# Sheet1.net
KiCad netlist of a schematic drawn in Altium Designer
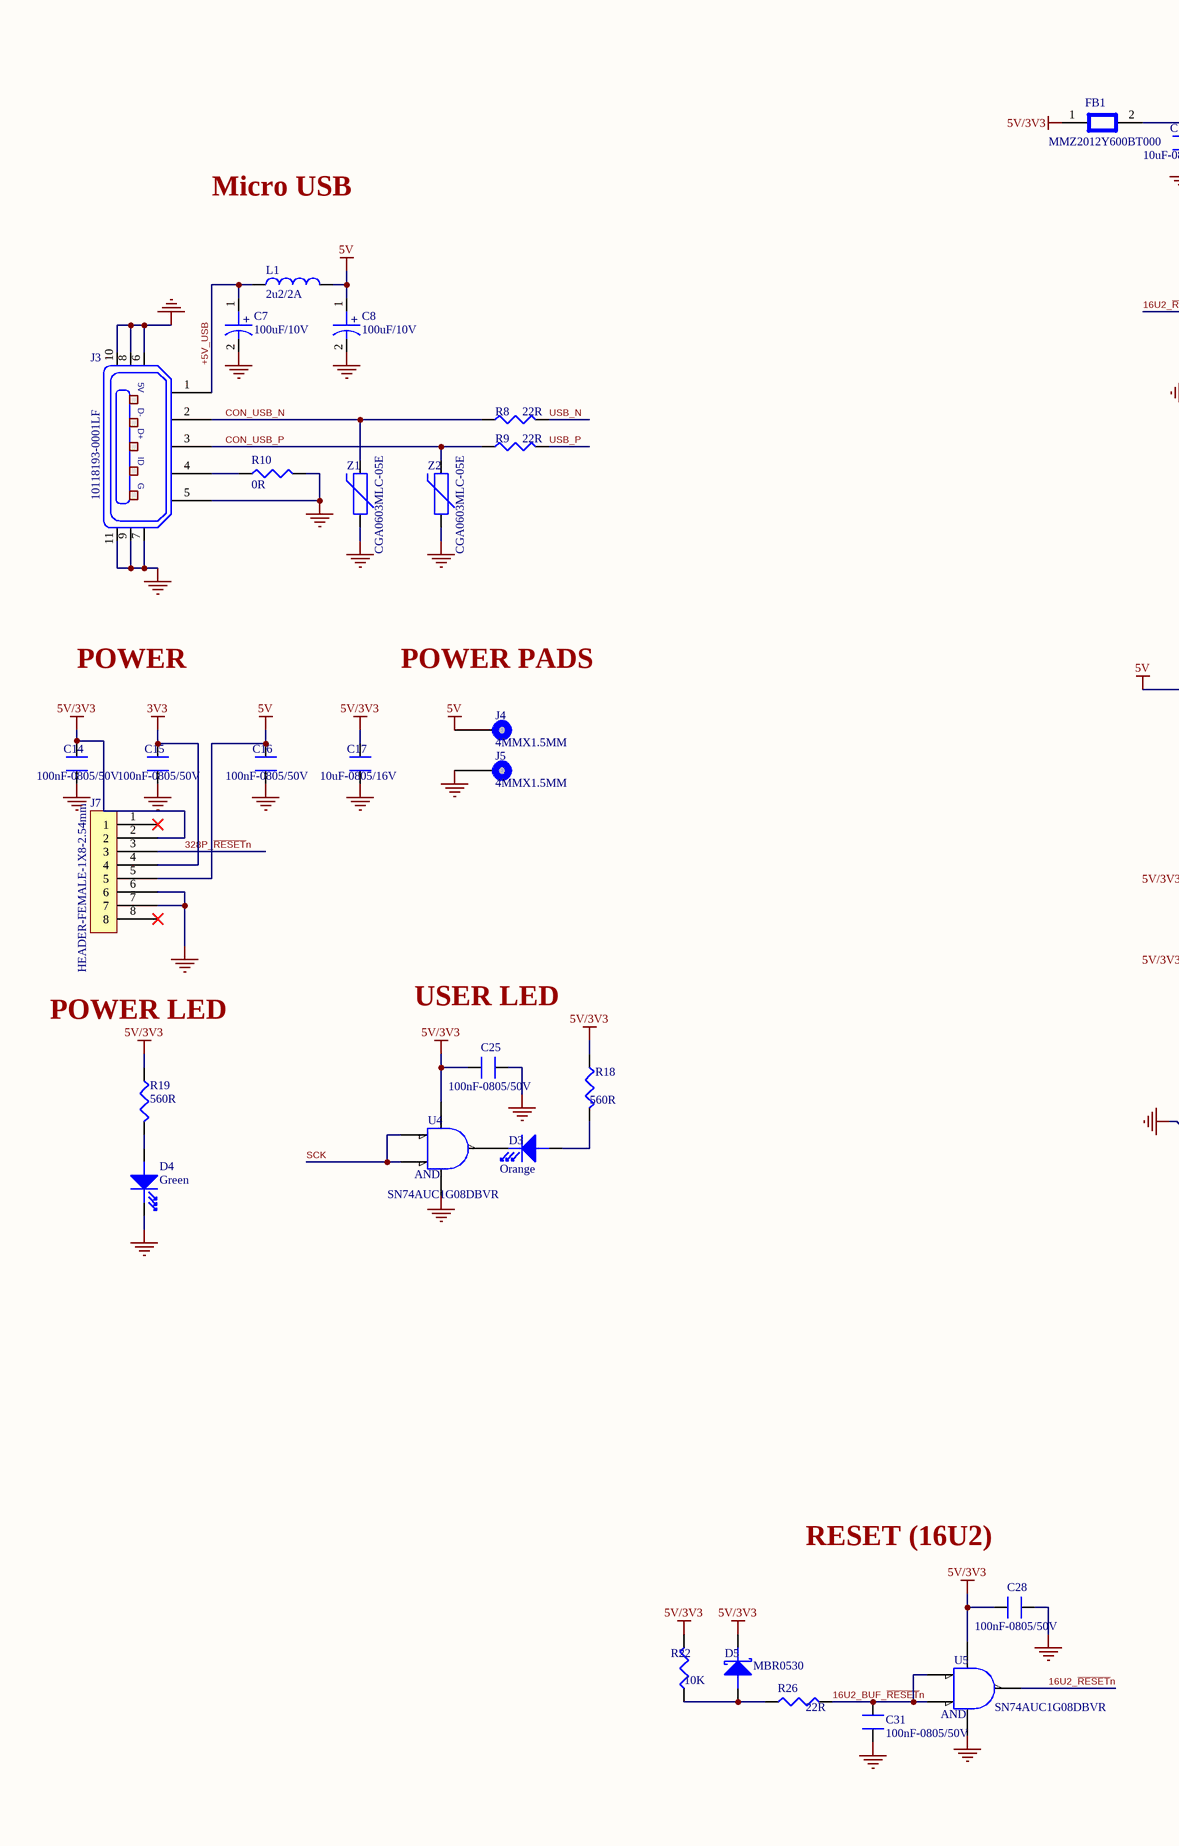
[diagram p0: Sheet1.SchDoc, left]
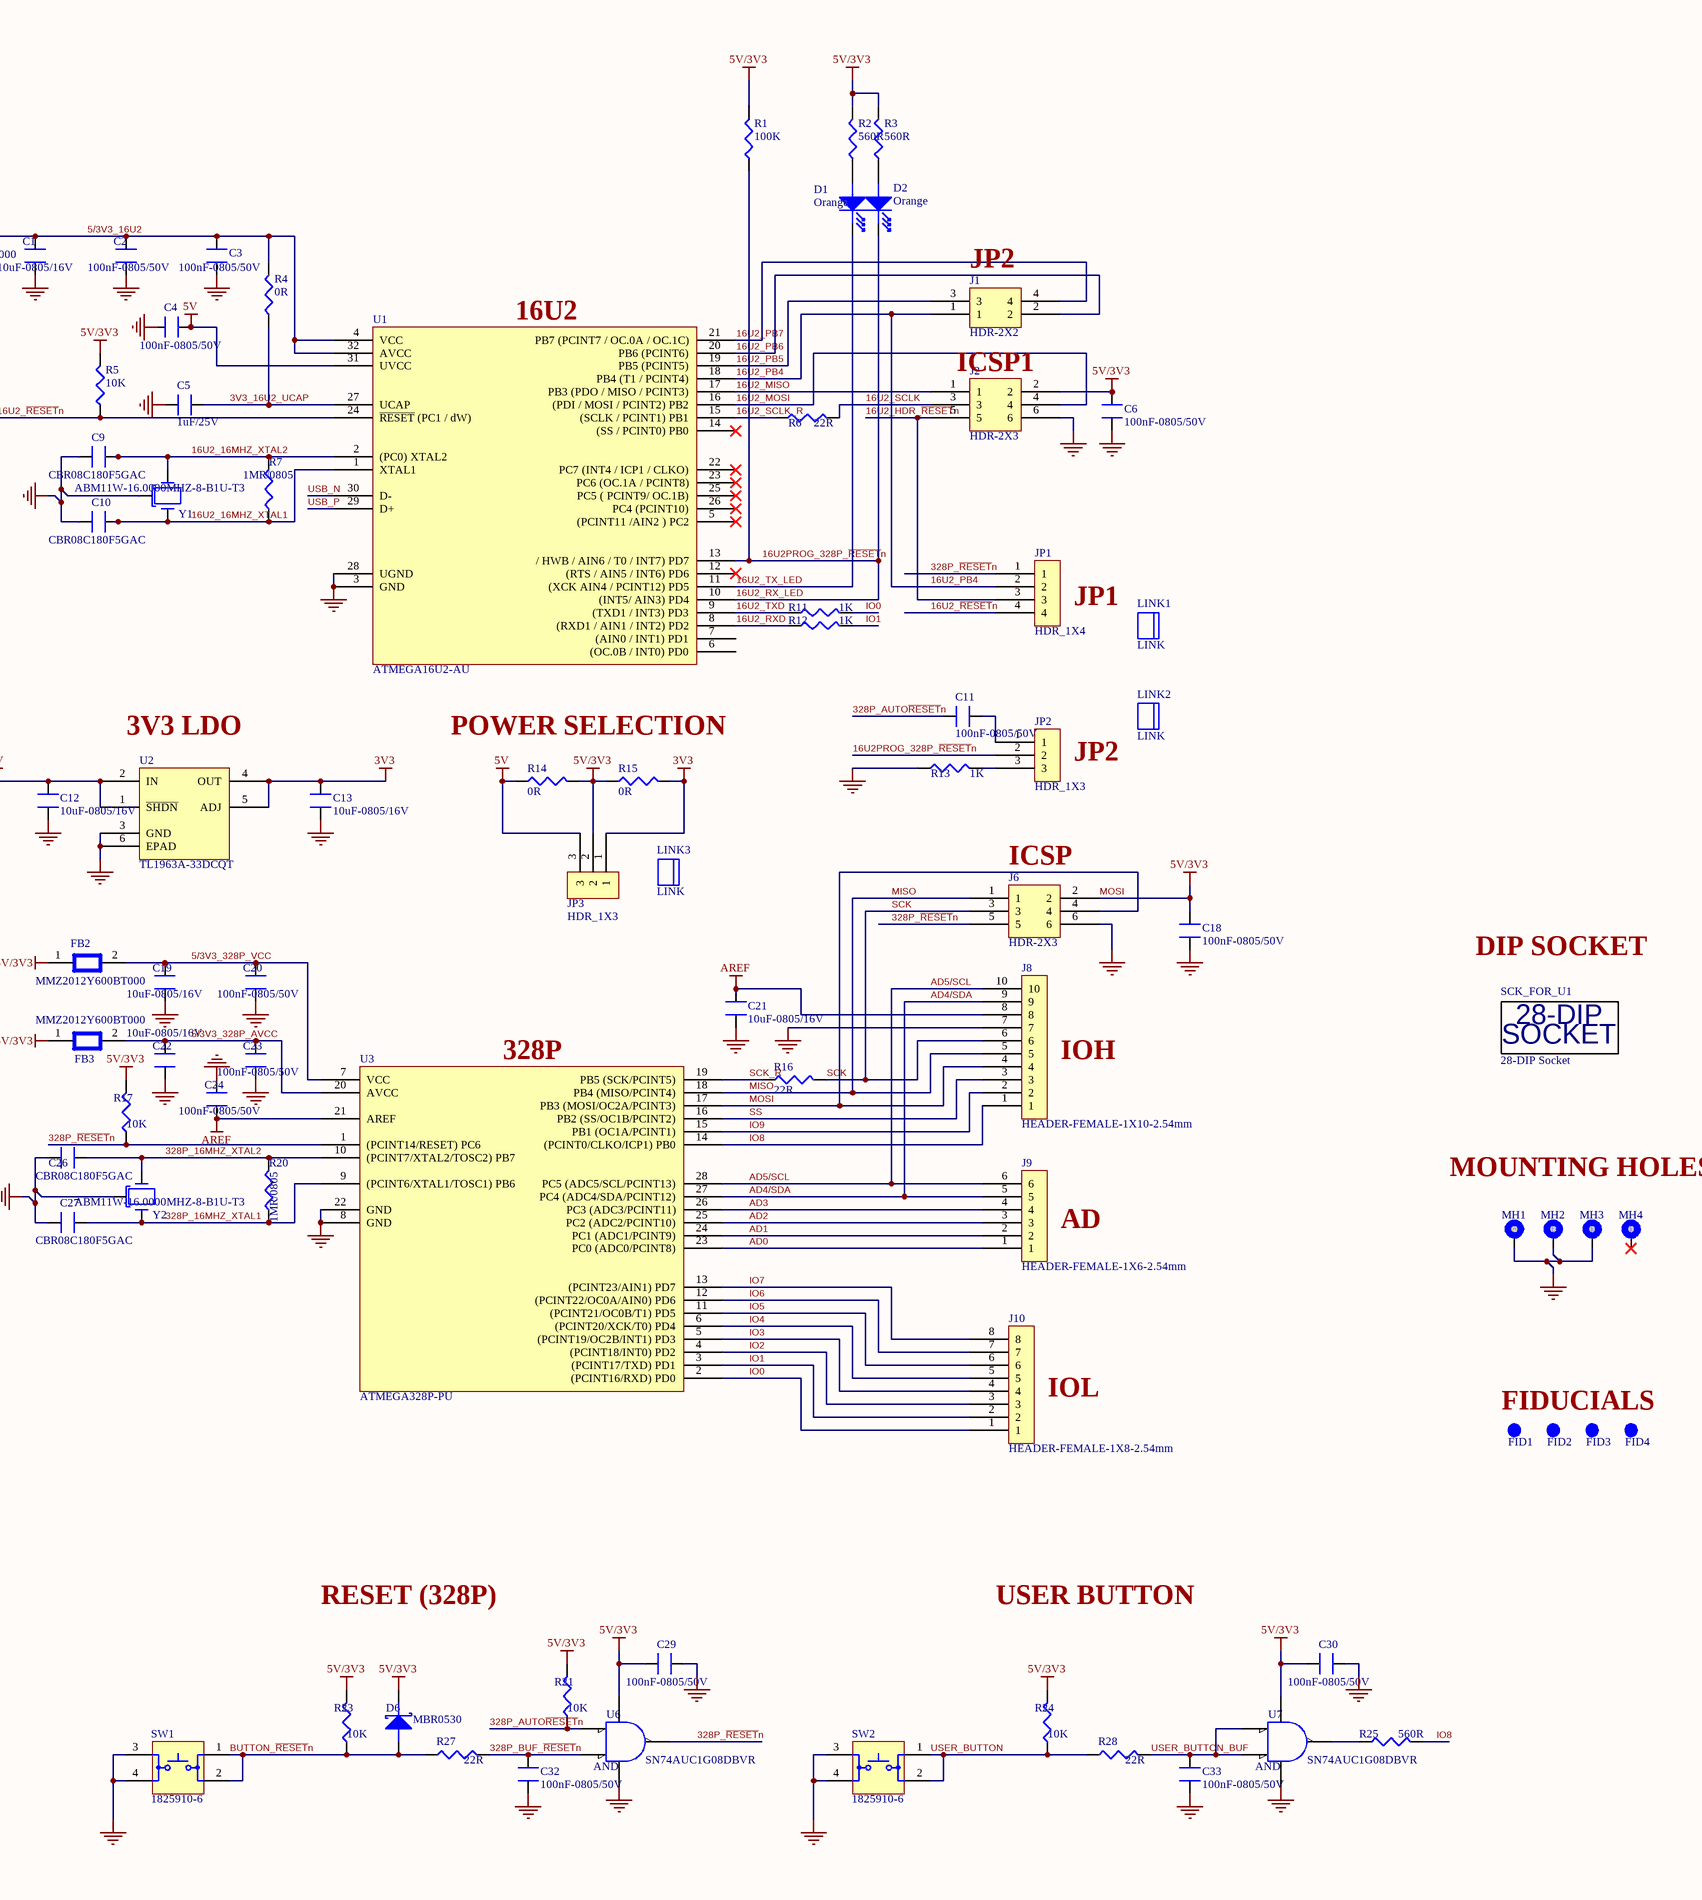
[diagram p1: Sheet1.SchDoc, right]

(export (version "E")
  (design (tool "Eeschema 10.0.6"))
  (components
    (comp (ref "C1")
      (value "10uF-0805/16V")
      (footprint "C0805")
      (fields
        (field (name "MANUFACTURER") "TDK")
        (field (name "MANUFACTURER PART NUMBER") "C2012X5R1C106M085AC")
        (field (name "TOLERANCE") "20%")
      )
      (libsource (lib "Schlib1") (part "C2012X5R1C106M085AC"))
    )
    (comp (ref "C2")
      (value "100nF-0805/50V")
      (footprint "C0805")
      (fields
        (field (name "MANUFACTURER") "TDK")
        (field (name "MANUFACTURER PART NUMBER") "C2012X7R1H104K125AE")
        (field (name "TOLERANCE") "10%")
      )
      (libsource (lib "Schlib1") (part "C2012X7R1H104K125AE"))
    )
    (comp (ref "C3")
      (value "100nF-0805/50V")
      (footprint "C0805")
      (fields
        (field (name "MANUFACTURER") "TDK")
        (field (name "MANUFACTURER PART NUMBER") "C2012X7R1H104K125AE")
        (field (name "TOLERANCE") "10%")
      )
      (libsource (lib "Schlib1") (part "C2012X7R1H104K125AE"))
    )
    (comp (ref "C4")
      (value "100nF-0805/50V")
      (footprint "C0805")
      (fields
        (field (name "MANUFACTURER") "TDK")
        (field (name "MANUFACTURER PART NUMBER") "C2012X7R1H104K125AE")
        (field (name "TOLERANCE") "10%")
      )
      (libsource (lib "Schlib1") (part "C2012X7R1H104K125AE"))
    )
    (comp (ref "C5")
      (value "1uF/25V")
      (footprint "C0805")
      (description "CAP CER 1UF 25V JB 0805")
      (fields
        (field (name "MANUFACTURER") "TDK")
        (field (name "MANUFACTURER PART NUMBER") "CGB4B3JB1E105K055AB")
      )
      (libsource (lib "Schlib1") (part "CGB4B3JB1E105K055AB"))
    )
    (comp (ref "C6")
      (value "100nF-0805/50V")
      (footprint "C0805")
      (fields
        (field (name "MANUFACTURER") "TDK")
        (field (name "MANUFACTURER PART NUMBER") "C2012X7R1H104K125AE")
        (field (name "TOLERANCE") "10%")
      )
      (libsource (lib "Schlib1") (part "C2012X7R1H104K125AE"))
    )
    (comp (ref "C7")
      (value "100uF/10V")
      (footprint "C_ALU_E_SIZE")
      (description "Cap Aluminum Lytic 100uF 10V 20% (8 X 6.2mm) SMD 110mA 1000h 105C T/R")
      (fields
        (field (name "MANUFACTURER") "Panasonic")
        (field (name "MANUFACTURER PART NUMBER") "EEE-HA1A101AP")
      )
      (libsource (lib "Schlib1") (part "EEE-HA1A101AP"))
    )
    (comp (ref "C8")
      (value "100uF/10V")
      (footprint "C_ALU_E_SIZE")
      (description "Cap Aluminum Lytic 100uF 10V 20% (8 X 6.2mm) SMD 110mA 1000h 105C T/R")
      (fields
        (field (name "MANUFACTURER") "Panasonic")
        (field (name "MANUFACTURER PART NUMBER") "EEE-HA1A101AP")
      )
      (libsource (lib "Schlib1") (part "EEE-HA1A101AP"))
    )
    (comp (ref "C9")
      (value "CBR08C180F5GAC")
      (footprint "C0805")
      (description "CAP CER 18PF 50V NP0 0805")
      (fields (field (name "MANUFACTURER") "KEMET") (field (name "TOLERANCE") "1%"))
      (libsource (lib "Schlib1") (part "CBR08C180F5GAC"))
    )
    (comp (ref "C10")
      (value "CBR08C180F5GAC")
      (footprint "C0805")
      (description "CAP CER 18PF 50V NP0 0805")
      (fields (field (name "MANUFACTURER") "KEMET") (field (name "TOLERANCE") "1%"))
      (libsource (lib "Schlib1") (part "CBR08C180F5GAC"))
    )
    (comp (ref "C11")
      (value "100nF-0805/50V")
      (footprint "C0805")
      (fields
        (field (name "MANUFACTURER") "TDK")
        (field (name "MANUFACTURER PART NUMBER") "C2012X7R1H104K125AE")
        (field (name "TOLERANCE") "10%")
      )
      (libsource (lib "Schlib1") (part "C2012X7R1H104K125AE"))
    )
    (comp (ref "C12")
      (value "10uF-0805/16V")
      (footprint "C0805")
      (fields
        (field (name "MANUFACTURER") "TDK")
        (field (name "MANUFACTURER PART NUMBER") "C2012X5R1C106M085AC")
        (field (name "TOLERANCE") "20%")
      )
      (libsource (lib "Schlib1") (part "C2012X5R1C106M085AC"))
    )
    (comp (ref "C13")
      (value "10uF-0805/16V")
      (footprint "C0805")
      (fields
        (field (name "MANUFACTURER") "TDK")
        (field (name "MANUFACTURER PART NUMBER") "C2012X5R1C106M085AC")
        (field (name "TOLERANCE") "20%")
      )
      (libsource (lib "Schlib1") (part "C2012X5R1C106M085AC"))
    )
    (comp (ref "C14")
      (value "100nF-0805/50V")
      (footprint "C0805")
      (fields
        (field (name "MANUFACTURER") "TDK")
        (field (name "MANUFACTURER PART NUMBER") "C2012X7R1H104K125AE")
        (field (name "TOLERANCE") "10%")
      )
      (libsource (lib "Schlib1") (part "C2012X7R1H104K125AE"))
    )
    (comp (ref "C15")
      (value "100nF-0805/50V")
      (footprint "C0805")
      (fields
        (field (name "MANUFACTURER") "TDK")
        (field (name "MANUFACTURER PART NUMBER") "C2012X7R1H104K125AE")
        (field (name "TOLERANCE") "10%")
      )
      (libsource (lib "Schlib1") (part "C2012X7R1H104K125AE"))
    )
    (comp (ref "C16")
      (value "100nF-0805/50V")
      (footprint "C0805")
      (fields
        (field (name "MANUFACTURER") "TDK")
        (field (name "MANUFACTURER PART NUMBER") "C2012X7R1H104K125AE")
        (field (name "TOLERANCE") "10%")
      )
      (libsource (lib "Schlib1") (part "C2012X7R1H104K125AE"))
    )
    (comp (ref "C17")
      (value "10uF-0805/16V")
      (footprint "C0805")
      (fields
        (field (name "MANUFACTURER") "TDK")
        (field (name "MANUFACTURER PART NUMBER") "C2012X5R1C106M085AC")
        (field (name "TOLERANCE") "20%")
      )
      (libsource (lib "Schlib1") (part "C2012X5R1C106M085AC"))
    )
    (comp (ref "C18")
      (value "100nF-0805/50V")
      (footprint "C0805")
      (fields
        (field (name "MANUFACTURER") "TDK")
        (field (name "MANUFACTURER PART NUMBER") "C2012X7R1H104K125AE")
        (field (name "TOLERANCE") "10%")
      )
      (libsource (lib "Schlib1") (part "C2012X7R1H104K125AE"))
    )
    (comp (ref "C19")
      (value "10uF-0805/16V")
      (footprint "C0805")
      (fields
        (field (name "MANUFACTURER") "TDK")
        (field (name "MANUFACTURER PART NUMBER") "C2012X5R1C106M085AC")
        (field (name "TOLERANCE") "20%")
      )
      (libsource (lib "Schlib1") (part "C2012X5R1C106M085AC"))
    )
    (comp (ref "C20")
      (value "100nF-0805/50V")
      (footprint "C0805")
      (fields
        (field (name "MANUFACTURER") "TDK")
        (field (name "MANUFACTURER PART NUMBER") "C2012X7R1H104K125AE")
        (field (name "TOLERANCE") "10%")
      )
      (libsource (lib "Schlib1") (part "C2012X7R1H104K125AE"))
    )
    (comp (ref "C21")
      (value "10uF-0805/16V")
      (footprint "C0805")
      (fields
        (field (name "MANUFACTURER") "TDK")
        (field (name "MANUFACTURER PART NUMBER") "C2012X5R1C106M085AC")
        (field (name "TOLERANCE") "20%")
      )
      (libsource (lib "Schlib1") (part "C2012X5R1C106M085AC"))
    )
    (comp (ref "C22")
      (value "10uF-0805/16V")
      (footprint "C0805")
      (fields
        (field (name "MANUFACTURER") "TDK")
        (field (name "MANUFACTURER PART NUMBER") "C2012X5R1C106M085AC")
        (field (name "TOLERANCE") "20%")
      )
      (libsource (lib "Schlib1") (part "C2012X5R1C106M085AC"))
    )
    (comp (ref "C23")
      (value "100nF-0805/50V")
      (footprint "C0805")
      (fields
        (field (name "MANUFACTURER") "TDK")
        (field (name "MANUFACTURER PART NUMBER") "C2012X7R1H104K125AE")
        (field (name "TOLERANCE") "10%")
      )
      (libsource (lib "Schlib1") (part "C2012X7R1H104K125AE"))
    )
    (comp (ref "C24")
      (value "100nF-0805/50V")
      (footprint "C0805")
      (fields
        (field (name "MANUFACTURER") "TDK")
        (field (name "MANUFACTURER PART NUMBER") "C2012X7R1H104K125AE")
        (field (name "TOLERANCE") "10%")
      )
      (libsource (lib "Schlib1") (part "C2012X7R1H104K125AE"))
    )
    (comp (ref "C25")
      (value "100nF-0805/50V")
      (footprint "C0805")
      (fields
        (field (name "MANUFACTURER") "TDK")
        (field (name "MANUFACTURER PART NUMBER") "C2012X7R1H104K125AE")
        (field (name "TOLERANCE") "10%")
      )
      (libsource (lib "Schlib1") (part "C2012X7R1H104K125AE"))
    )
    (comp (ref "C26")
      (value "CBR08C180F5GAC")
      (footprint "C0805")
      (description "CAP CER 18PF 50V NP0 0805")
      (fields (field (name "MANUFACTURER") "KEMET") (field (name "TOLERANCE") "1%"))
      (libsource (lib "Schlib1") (part "CBR08C180F5GAC"))
    )
    (comp (ref "C27")
      (value "CBR08C180F5GAC")
      (footprint "C0805")
      (description "CAP CER 18PF 50V NP0 0805")
      (fields (field (name "MANUFACTURER") "KEMET") (field (name "TOLERANCE") "1%"))
      (libsource (lib "Schlib1") (part "CBR08C180F5GAC"))
    )
    (comp (ref "C28")
      (value "100nF-0805/50V")
      (footprint "C0805")
      (fields
        (field (name "MANUFACTURER") "TDK")
        (field (name "MANUFACTURER PART NUMBER") "C2012X7R1H104K125AE")
        (field (name "TOLERANCE") "10%")
      )
      (libsource (lib "Schlib1") (part "C2012X7R1H104K125AE"))
    )
    (comp (ref "C29")
      (value "100nF-0805/50V")
      (footprint "C0805")
      (fields
        (field (name "MANUFACTURER") "TDK")
        (field (name "MANUFACTURER PART NUMBER") "C2012X7R1H104K125AE")
        (field (name "TOLERANCE") "10%")
      )
      (libsource (lib "Schlib1") (part "C2012X7R1H104K125AE"))
    )
    (comp (ref "C30")
      (value "100nF-0805/50V")
      (footprint "C0805")
      (fields
        (field (name "MANUFACTURER") "TDK")
        (field (name "MANUFACTURER PART NUMBER") "C2012X7R1H104K125AE")
        (field (name "TOLERANCE") "10%")
      )
      (libsource (lib "Schlib1") (part "C2012X7R1H104K125AE"))
    )
    (comp (ref "C31")
      (value "100nF-0805/50V")
      (footprint "C0805")
      (fields
        (field (name "MANUFACTURER") "TDK")
        (field (name "MANUFACTURER PART NUMBER") "C2012X7R1H104K125AE")
        (field (name "TOLERANCE") "10%")
      )
      (libsource (lib "Schlib1") (part "C2012X7R1H104K125AE"))
    )
    (comp (ref "C32")
      (value "100nF-0805/50V")
      (footprint "C0805")
      (fields
        (field (name "MANUFACTURER") "TDK")
        (field (name "MANUFACTURER PART NUMBER") "C2012X7R1H104K125AE")
        (field (name "TOLERANCE") "10%")
      )
      (libsource (lib "Schlib1") (part "C2012X7R1H104K125AE"))
    )
    (comp (ref "C33")
      (value "100nF-0805/50V")
      (footprint "C0805")
      (fields
        (field (name "MANUFACTURER") "TDK")
        (field (name "MANUFACTURER PART NUMBER") "C2012X7R1H104K125AE")
        (field (name "TOLERANCE") "10%")
      )
      (libsource (lib "Schlib1") (part "C2012X7R1H104K125AE"))
    )
    (comp (ref "D1")
      (value "Orange")
      (footprint "LED-0603")
      (description "OSRAM - LO L29K-H2K1-24-Z - SMARTLED 0603 ORANGE 55AC2374")
      (fields
        (field (name "MANUFACTURER") "Osram Opto")
        (field (name "MANUFACTURER PART NUMBER") "LOL29K-H2K1-24-Z")
      )
      (libsource (lib "Schlib1") (part "LOL29K-H2K1-24-Z"))
    )
    (comp (ref "D2")
      (value "Orange")
      (footprint "LED-0603")
      (description "OSRAM - LO L29K-H2K1-24-Z - SMARTLED 0603 ORANGE 55AC2374")
      (fields
        (field (name "MANUFACTURER") "Osram Opto")
        (field (name "MANUFACTURER PART NUMBER") "LOL29K-H2K1-24-Z")
      )
      (libsource (lib "Schlib1") (part "LOL29K-H2K1-24-Z"))
    )
    (comp (ref "D3")
      (value "Orange")
      (footprint "LED-0603")
      (description "OSRAM - LO L29K-H2K1-24-Z - SMARTLED 0603 ORANGE 55AC2374")
      (fields
        (field (name "MANUFACTURER") "Osram Opto")
        (field (name "MANUFACTURER PART NUMBER") "LOL29K-H2K1-24-Z")
      )
      (libsource (lib "Schlib1") (part "LOL29K-H2K1-24-Z"))
    )
    (comp (ref "D4")
      (value "Green")
      (footprint "LED-0603")
      (description "LED GREEN DIFFUSED 0603 SMD")
      (fields
        (field (name "MANUFACTURER") "Osram Opto")
        (field (name "MANUFACTURER PART NUMBER") "LTQ39E-Q1OO-25-1")
      )
      (libsource (lib "Schlib1") (part "LTQ39E-Q1OO-25-1"))
    )
    (comp (ref "D5")
      (value "MBR0530")
      (footprint "SOD-123")
      (description "DIODE SCHOTTKY 30V 500MA SOD123")
      (fields (field (name "MANUFACTURER") "ON Semiconductor / Fairchild"))
      (libsource (lib "Schlib1") (part "MBR0530"))
    )
    (comp (ref "D6")
      (value "MBR0530")
      (footprint "SOD-123")
      (description "DIODE SCHOTTKY 30V 500MA SOD123")
      (fields (field (name "MANUFACTURER") "ON Semiconductor / Fairchild"))
      (libsource (lib "Schlib1") (part "MBR0530"))
    )
    (comp (ref "FB1")
      (value "MMZ2012Y600BT000")
      (footprint "C0805")
      (description "TDK         MMZ2012Y600BT000             FERRITE BEAD, 60 OHM, 1A, 0805")
      (fields (field (name "MANUFACTURER") "TDK") (field (name "TOLERANCE") "25%"))
      (libsource (lib "Schlib1") (part "MMZ2012Y600BT000"))
    )
    (comp (ref "FB2")
      (value "MMZ2012Y600BT000")
      (footprint "C0805")
      (description "TDK         MMZ2012Y600BT000             FERRITE BEAD, 60 OHM, 1A, 0805")
      (fields (field (name "MANUFACTURER") "TDK") (field (name "TOLERANCE") "25%"))
      (libsource (lib "Schlib1") (part "MMZ2012Y600BT000"))
    )
    (comp (ref "FB3")
      (value "MMZ2012Y600BT000")
      (footprint "C0805")
      (description "TDK         MMZ2012Y600BT000             FERRITE BEAD, 60 OHM, 1A, 0805")
      (fields (field (name "MANUFACTURER") "TDK") (field (name "TOLERANCE") "25%"))
      (libsource (lib "Schlib1") (part "MMZ2012Y600BT000"))
    )
    (comp (ref "FID1")
      (value "FID_1MMC")
      (footprint "FID_40X120D")
      (description "Fiducial 40 mil Diameter, 120 mil Mask")
      (libsource (lib "Schlib1") (part "FID-1MMC"))
    )
    (comp (ref "FID2")
      (value "FID_1MMC")
      (footprint "FID_40X120D")
      (description "Fiducial 40 mil Diameter, 120 mil Mask")
      (libsource (lib "Schlib1") (part "FID-1MMC"))
    )
    (comp (ref "FID3")
      (value "FID_1MMC")
      (footprint "FID_40X120D")
      (description "Fiducial 40 mil Diameter, 120 mil Mask")
      (libsource (lib "Schlib1") (part "FID-1MMC"))
    )
    (comp (ref "FID4")
      (value "FID_1MMC")
      (footprint "FID_40X120D")
      (description "Fiducial 40 mil Diameter, 120 mil Mask")
      (libsource (lib "Schlib1") (part "FID-1MMC"))
    )
    (comp (ref "J1")
      (value "HDR-2X2")
      (footprint "HDR-2X2-2.54MM")
      (description "CONN HEADER 4POS .100 DUAL GOLD")
      (fields
        (field (name "MANUFACTURER") "Samtec")
        (field (name "MANUFACTURER PART NUMBER") "TSW-102-23-S-D")
      )
      (libsource (lib "Schlib1") (part "TSW-102-23-S-D"))
    )
    (comp (ref "J2")
      (value "HDR-2X3")
      (footprint "HDR-2X3-2.54MM")
      (fields
        (field (name "MANUFACTURER") "Samtec")
        (field (name "MANUFACTURER PART NUMBER") "TSW-103-06-T-D")
      )
      (libsource (lib "Schlib1") (part "TSW-103-06-T-D"))
    )
    (comp (ref "J3")
      (value "10118193-0001LF")
      (footprint "USB-A")
      (description "CONN USB MICRO B RECPT SMT R/A")
      (fields (field (name "MANUFACTURER") "Amphenol ICC / FCI"))
      (libsource (lib "Schlib1") (part "10118193-0001LF"))
    )
    (comp (ref "J4")
      (value "4MMX1.5MM")
      (footprint "PAD_WITH_HOLE_4MMX1.5MM")
      (description "Pad with a hole 4mm x 1.5mm")
      (libsource (lib "Schlib1") (part "PAD_WITH_HOLE_4MMX1.5MM"))
    )
    (comp (ref "J5")
      (value "4MMX1.5MM")
      (footprint "PAD_WITH_HOLE_4MMX1.5MM")
      (description "Pad with a hole 4mm x 1.5mm")
      (libsource (lib "Schlib1") (part "PAD_WITH_HOLE_4MMX1.5MM"))
    )
    (comp (ref "J6")
      (value "HDR-2X3")
      (footprint "HDR-2X3-2.54MM")
      (fields
        (field (name "MANUFACTURER") "Samtec")
        (field (name "MANUFACTURER PART NUMBER") "TSW-103-06-T-D")
      )
      (libsource (lib "Schlib1") (part "TSW-103-06-T-D"))
    )
    (comp (ref "J7")
      (value "HEADER-FEMALE-1X8-2.54mm")
      (footprint "FEMALE-1X8-2.54mm")
      (description "CONN HDR 8POS 0.1 TIN PCB")
      (fields
        (field (name "MANUFACTURER") "Sullins")
        (field (name "MANUFACTURER PART NUMBER") "PPTC081LFBN-RC")
      )
      (libsource (lib "") (part "PPTC081LFBN-RC_1"))
    )
    (comp (ref "J8")
      (value "HEADER-FEMALE-1X10-2.54mm")
      (footprint "FEMALE-1X10-2.54mm")
      (description "CONN HDR 10POS 0.1 GOLD PCB")
      (fields
        (field (name "MANUFACTURER") "Sullins")
        (field (name "MANUFACTURER PART NUMBER") "PPPC101LFBN-RC")
      )
      (libsource (lib "Schlib1") (part "PPPC101LFBN-RC"))
    )
    (comp (ref "J9")
      (value "HEADER-FEMALE-1X6-2.54mm")
      (footprint "FEMALE-1X6-2.54mm")
      (description "CONN HDR 6POS 0.1 GOLD PCB")
      (fields
        (field (name "MANUFACTURER") "Sullins")
        (field (name "MANUFACTURER PART NUMBER") "PPPC061LFBN-RC")
      )
      (libsource (lib "Schlib1") (part "PPPC061LFBN-RC"))
    )
    (comp (ref "J10")
      (value "HEADER-FEMALE-1X8-2.54mm")
      (footprint "FEMALE-1X8-2.54mm")
      (description "CONN HDR 8POS 0.1 TIN PCB")
      (fields
        (field (name "MANUFACTURER") "Sullins")
        (field (name "MANUFACTURER PART NUMBER") "PPTC081LFBN-RC")
      )
      (libsource (lib "Schlib1") (part "PPTC081LFBN-RC"))
    )
    (comp (ref "JP1")
      (value "HDR_1X4")
      (footprint "HDR-1X4-2.54mm")
      (description "CONN HEADER 4POS .100 STR 15AU")
      (fields
        (field (name "MANUFACTURER") "Amphenol ICC / FCI")
        (field (name "MANUFACTURER PART NUMBER") "68002-204HLF")
      )
      (libsource (lib "Schlib1") (part "68002-204HLF"))
    )
    (comp (ref "JP2")
      (value "HDR_1X3")
      (footprint "FEMALE-1X3-2.54mm")
      (description "METZ CONNECT - PR20203VBNN - CONNECTOR, HEADER, 3POS, 1ROW, 2.54MM")
      (fields
        (field (name "MANUFACTURER") "METZ CONNECT")
        (field (name "MANUFACTURER PART NUMBER") "PR20203VBNN")
      )
      (libsource (lib "Schlib1") (part "PR20203VBNN"))
    )
    (comp (ref "JP3")
      (value "HDR_1X3")
      (footprint "FEMALE-1X3-2.54mm")
      (description "METZ CONNECT - PR20203VBNN - CONNECTOR, HEADER, 3POS, 1ROW, 2.54MM")
      (fields
        (field (name "MANUFACTURER") "METZ CONNECT")
        (field (name "MANUFACTURER PART NUMBER") "PR20203VBNN")
      )
      (libsource (lib "") (part "PR20203VBNN_1"))
    )
    (comp (ref "L1")
      (value "2u2/2A")
      (footprint "C1210_IND")
      (description "FIXED IND 2.2UH 2A 80 MOHM SMD")
      (fields
        (field (name "MANUFACTURER") "KEMET")
        (field (name "MANUFACTURER PART NUMBER") "L1210R2R2MDWIT")
      )
      (libsource (lib "Schlib1") (part "L1210R2R2MDWIT"))
    )
    (comp (ref "LINK1")
      (value "LINK")
      (description "CONN JUMPER SHORTING .100\" GOLD")
      (fields
        (field (name "MANUFACTURER") "Sullins")
        (field (name "MANUFACTURER PART NUMBER") "QPC02SXGN-RC")
      )
      (libsource (lib "Schlib1") (part "QPC02SXGN-RC"))
    )
    (comp (ref "LINK2")
      (value "LINK")
      (description "CONN JUMPER SHORTING .100\" GOLD")
      (fields
        (field (name "MANUFACTURER") "Sullins")
        (field (name "MANUFACTURER PART NUMBER") "QPC02SXGN-RC")
      )
      (libsource (lib "Schlib1") (part "QPC02SXGN-RC"))
    )
    (comp (ref "LINK3")
      (value "LINK")
      (description "CONN JUMPER SHORTING .100\" GOLD")
      (fields
        (field (name "MANUFACTURER") "Sullins")
        (field (name "MANUFACTURER PART NUMBER") "QPC02SXGN-RC")
      )
      (libsource (lib "Schlib1") (part "QPC02SXGN-RC"))
    )
    (comp (ref "MH1")
      (value "MH_7.4MMC_3.2MMD")
      (footprint "MH_7.4MMC_3.2MMD")
      (description "Mounting Hole 7.4 mm Diameter, 3.2 mm Drill")
      (libsource (lib "Schlib1") (part "MH_7.4MMC_3.2MMD"))
    )
    (comp (ref "MH2")
      (value "MH_7.4MMC_3.2MMD")
      (footprint "MH_7.4MMC_3.2MMD")
      (description "Mounting Hole 7.4 mm Diameter, 3.2 mm Drill")
      (libsource (lib "Schlib1") (part "MH_7.4MMC_3.2MMD"))
    )
    (comp (ref "MH3")
      (value "MH_7.4MMC_3.2MMD")
      (footprint "MH_7.4MMC_3.2MMD")
      (description "Mounting Hole 7.4 mm Diameter, 3.2 mm Drill")
      (libsource (lib "Schlib1") (part "MH_7.4MMC_3.2MMD"))
    )
    (comp (ref "MH4")
      (value "MH_7.4MMC_3.2MMD")
      (footprint "MH_7.4MMC_3.2MMD_NON_COPPER_NPLT")
      (description "Mounting Hole 7.4 mm Diameter (Non Copper), 3.2 mm Drill NPTH")
      (libsource (lib "Schlib1") (part "MH_7.4MMNC_3.2MMD"))
    )
    (comp (ref "R1")
      (value "100K")
      (footprint "R0805")
      (description "Res Thick Film 0805 100K Ohm 1% 1/8W ±100ppm/°C Molded SMD SMD Paper T/R")
      (fields
        (field (name "MANUFACTURER") "Yageo")
        (field (name "MANUFACTURER PART NUMBER") "AC0805FR-07100KL")
      )
      (libsource (lib "Schlib1") (part "AC0805FR-07100KL"))
    )
    (comp (ref "R2")
      (value "560R")
      (footprint "R0805")
      (description "Thick Film Resistors - SMD 1/8W 560ohm 1% AEC-Q200")
      (fields
        (field (name "MANUFACTURER") "Yageo")
        (field (name "MANUFACTURER PART NUMBER") "AC0805FR-07560RL")
      )
      (libsource (lib "Schlib1") (part "AC0805FR-07560RL"))
    )
    (comp (ref "R3")
      (value "560R")
      (footprint "R0805")
      (description "Thick Film Resistors - SMD 1/8W 560ohm 1% AEC-Q200")
      (fields
        (field (name "MANUFACTURER") "Yageo")
        (field (name "MANUFACTURER PART NUMBER") "AC0805FR-07560RL")
      )
      (libsource (lib "Schlib1") (part "AC0805FR-07560RL"))
    )
    (comp (ref "R4")
      (value "0R")
      (footprint "R0805")
      (description "Res Thick Film 0805 0 Ohm Epoxy Pad SMD T/R")
      (fields
        (field (name "MANUFACTURER") "Yageo")
        (field (name "MANUFACTURER PART NUMBER") "RC0805FR-070RL")
      )
      (libsource (lib "Schlib1") (part "RC0805FR-070RL"))
    )
    (comp (ref "R5")
      (value "10K")
      (footprint "R0805")
      (description "RES SMD 10K OHM 5% 1/8W 0805")
      (fields
        (field (name "MANUFACTURER") "Yageo")
        (field (name "MANUFACTURER PART NUMBER") "SR0805JR-0710KL")
      )
      (libsource (lib "Schlib1") (part "SR0805JR-0710KL"))
    )
    (comp (ref "R6")
      (value "22R")
      (footprint "R0805")
      (description "Res Thick Film 0805 22 Ohm 5% 1/8W 100ppm/C Molded SMD SMD Paper T/R")
      (fields
        (field (name "MANUFACTURER") "Yageo")
        (field (name "MANUFACTURER PART NUMBER") "RC0805JR-0722RL")
      )
      (libsource (lib "Schlib1") (part "RC0805JR-0722RL"))
    )
    (comp (ref "R7")
      (value "1MR/0805")
      (footprint "R0805")
      (description "RES SMD 1M OHM 1% 1/8W 0805")
      (fields
        (field (name "MANUFACTURER") "Yageo")
        (field (name "MANUFACTURER PART NUMBER") "RV0805FR-071ML")
      )
      (libsource (lib "Schlib1") (part "RV0805FR-071ML"))
    )
    (comp (ref "R8")
      (value "22R")
      (footprint "R0805")
      (description "Res Thick Film 0805 22 Ohm 5% 1/8W 100ppm/C Molded SMD SMD Paper T/R")
      (fields
        (field (name "MANUFACTURER") "Yageo")
        (field (name "MANUFACTURER PART NUMBER") "RC0805JR-0722RL")
      )
      (libsource (lib "Schlib1") (part "RC0805JR-0722RL"))
    )
    (comp (ref "R9")
      (value "22R")
      (footprint "R0805")
      (description "Res Thick Film 0805 22 Ohm 5% 1/8W 100ppm/C Molded SMD SMD Paper T/R")
      (fields
        (field (name "MANUFACTURER") "Yageo")
        (field (name "MANUFACTURER PART NUMBER") "RC0805JR-0722RL")
      )
      (libsource (lib "Schlib1") (part "RC0805JR-0722RL"))
    )
    (comp (ref "R10")
      (value "0R")
      (footprint "R0805")
      (description "Res Thick Film 0805 0 Ohm Epoxy Pad SMD T/R")
      (fields
        (field (name "MANUFACTURER") "Yageo")
        (field (name "MANUFACTURER PART NUMBER") "RC0805FR-070RL")
      )
      (libsource (lib "Schlib1") (part "RC0805FR-070RL"))
    )
    (comp (ref "R11")
      (value "1K")
      (footprint "R0805")
      (description "RES SMD 1K OHM 1% 1/8W 0805")
      (fields
        (field (name "MANUFACTURER") "Yageo")
        (field (name "MANUFACTURER PART NUMBER") "AC0805FR-071KL")
      )
      (libsource (lib "Schlib1") (part "AC0805FR-071KL"))
    )
    (comp (ref "R12")
      (value "1K")
      (footprint "R0805")
      (description "RES SMD 1K OHM 1% 1/8W 0805")
      (fields
        (field (name "MANUFACTURER") "Yageo")
        (field (name "MANUFACTURER PART NUMBER") "AC0805FR-071KL")
      )
      (libsource (lib "Schlib1") (part "AC0805FR-071KL"))
    )
    (comp (ref "R13")
      (value "1K")
      (footprint "R0805")
      (description "RES SMD 1K OHM 1% 1/8W 0805")
      (fields
        (field (name "MANUFACTURER") "Yageo")
        (field (name "MANUFACTURER PART NUMBER") "AC0805FR-071KL")
      )
      (libsource (lib "Schlib1") (part "AC0805FR-071KL"))
    )
    (comp (ref "R14")
      (value "0R")
      (footprint "R0805")
      (description "Res Thick Film 0805 0 Ohm Epoxy Pad SMD T/R")
      (fields
        (field (name "MANUFACTURER") "Yageo")
        (field (name "MANUFACTURER PART NUMBER") "RC0805FR-070RL")
      )
      (libsource (lib "Schlib1") (part "RC0805FR-070RL"))
    )
    (comp (ref "R15")
      (value "0R")
      (footprint "R0805")
      (description "Res Thick Film 0805 0 Ohm Epoxy Pad SMD T/R")
      (fields
        (field (name "MANUFACTURER") "Yageo")
        (field (name "MANUFACTURER PART NUMBER") "RC0805FR-070RL")
      )
      (libsource (lib "Schlib1") (part "RC0805FR-070RL"))
    )
    (comp (ref "R16")
      (value "22R")
      (footprint "R0805")
      (description "Res Thick Film 0805 22 Ohm 5% 1/8W 100ppm/C Molded SMD SMD Paper T/R")
      (fields
        (field (name "MANUFACTURER") "Yageo")
        (field (name "MANUFACTURER PART NUMBER") "RC0805JR-0722RL")
      )
      (libsource (lib "Schlib1") (part "RC0805JR-0722RL"))
    )
    (comp (ref "R17")
      (value "10K")
      (footprint "R0805")
      (description "RES SMD 10K OHM 5% 1/8W 0805")
      (fields
        (field (name "MANUFACTURER") "Yageo")
        (field (name "MANUFACTURER PART NUMBER") "SR0805JR-0710KL")
      )
      (libsource (lib "Schlib1") (part "SR0805JR-0710KL"))
    )
    (comp (ref "R18")
      (value "560R")
      (footprint "R0805")
      (description "Thick Film Resistors - SMD 1/8W 560ohm 1% AEC-Q200")
      (fields
        (field (name "MANUFACTURER") "Yageo")
        (field (name "MANUFACTURER PART NUMBER") "AC0805FR-07560RL")
      )
      (libsource (lib "Schlib1") (part "AC0805FR-07560RL"))
    )
    (comp (ref "R19")
      (value "560R")
      (footprint "R0805")
      (description "Thick Film Resistors - SMD 1/8W 560ohm 1% AEC-Q200")
      (fields
        (field (name "MANUFACTURER") "Yageo")
        (field (name "MANUFACTURER PART NUMBER") "AC0805FR-07560RL")
      )
      (libsource (lib "Schlib1") (part "AC0805FR-07560RL"))
    )
    (comp (ref "R20")
      (value "1MR/0805")
      (footprint "R0805")
      (description "RES SMD 1M OHM 1% 1/8W 0805")
      (fields
        (field (name "MANUFACTURER") "Yageo")
        (field (name "MANUFACTURER PART NUMBER") "RV0805FR-071ML")
      )
      (libsource (lib "Schlib1") (part "RV0805FR-071ML"))
    )
    (comp (ref "R21")
      (value "10K")
      (footprint "R0805")
      (description "RES SMD 10K OHM 5% 1/8W 0805")
      (fields
        (field (name "MANUFACTURER") "Yageo")
        (field (name "MANUFACTURER PART NUMBER") "SR0805JR-0710KL")
      )
      (libsource (lib "Schlib1") (part "SR0805JR-0710KL"))
    )
    (comp (ref "R22")
      (value "10K")
      (footprint "R0805")
      (description "RES SMD 10K OHM 5% 1/8W 0805")
      (fields
        (field (name "MANUFACTURER") "Yageo")
        (field (name "MANUFACTURER PART NUMBER") "SR0805JR-0710KL")
      )
      (libsource (lib "Schlib1") (part "SR0805JR-0710KL"))
    )
    (comp (ref "R23")
      (value "10K")
      (footprint "R0805")
      (description "RES SMD 10K OHM 5% 1/8W 0805")
      (fields
        (field (name "MANUFACTURER") "Yageo")
        (field (name "MANUFACTURER PART NUMBER") "SR0805JR-0710KL")
      )
      (libsource (lib "Schlib1") (part "SR0805JR-0710KL"))
    )
    (comp (ref "R24")
      (value "10K")
      (footprint "R0805")
      (description "RES SMD 10K OHM 5% 1/8W 0805")
      (fields
        (field (name "MANUFACTURER") "Yageo")
        (field (name "MANUFACTURER PART NUMBER") "SR0805JR-0710KL")
      )
      (libsource (lib "Schlib1") (part "SR0805JR-0710KL"))
    )
    (comp (ref "R25")
      (value "560R")
      (footprint "R0805")
      (description "Thick Film Resistors - SMD 1/8W 560ohm 1% AEC-Q200")
      (fields
        (field (name "MANUFACTURER") "Yageo")
        (field (name "MANUFACTURER PART NUMBER") "AC0805FR-07560RL")
      )
      (libsource (lib "Schlib1") (part "AC0805FR-07560RL"))
    )
    (comp (ref "R26")
      (value "22R")
      (footprint "R0805")
      (description "Res Thick Film 0805 22 Ohm 5% 1/8W 100ppm/C Molded SMD SMD Paper T/R")
      (fields
        (field (name "MANUFACTURER") "Yageo")
        (field (name "MANUFACTURER PART NUMBER") "RC0805JR-0722RL")
      )
      (libsource (lib "Schlib1") (part "RC0805JR-0722RL"))
    )
    (comp (ref "R27")
      (value "22R")
      (footprint "R0805")
      (description "Res Thick Film 0805 22 Ohm 5% 1/8W 100ppm/C Molded SMD SMD Paper T/R")
      (fields
        (field (name "MANUFACTURER") "Yageo")
        (field (name "MANUFACTURER PART NUMBER") "RC0805JR-0722RL")
      )
      (libsource (lib "Schlib1") (part "RC0805JR-0722RL"))
    )
    (comp (ref "R28")
      (value "22R")
      (footprint "R0805")
      (description "Res Thick Film 0805 22 Ohm 5% 1/8W 100ppm/C Molded SMD SMD Paper T/R")
      (fields
        (field (name "MANUFACTURER") "Yageo")
        (field (name "MANUFACTURER PART NUMBER") "RC0805JR-0722RL")
      )
      (libsource (lib "Schlib1") (part "RC0805JR-0722RL"))
    )
    (comp (ref "SCK_FOR_U1")
      (value "28-DIP Socket")
      (footprint "28_DIP_7.62mm_SOCKET")
      (description "CONN IC DIP SOCKET 28POS TIN")
      (fields (field (name "MANUFACTURER") "3M") (field (name "MANUFACTURER PART NUMBER") "4828-3004-CP"))
      (libsource (lib "Schlib1") (part "4828-3004-CP"))
    )
    (comp (ref "SW1")
      (value "1825910-6")
      (footprint "1825910-6")
      (description "6X6, H5,  160G TAC.SWITCH")
      (fields (field (name "MANUFACTURER") "TE Connectivity Alcoswitch"))
      (libsource (lib "Schlib1") (part "1825910-6"))
    )
    (comp (ref "SW2")
      (value "1825910-6")
      (footprint "1825910-6")
      (description "6X6, H5,  160G TAC.SWITCH")
      (fields (field (name "MANUFACTURER") "TE Connectivity Alcoswitch"))
      (libsource (lib "Schlib1") (part "1825910-6"))
    )
    (comp (ref "U1")
      (value "ATMEGA16U2-AU")
      (footprint "TQFP32")
      (description "MICROCHIP - ATMEGA16U2-AU - MCU, 8BIT, MEGAAVR, 16MHZ, TQFP-32")
      (fields (field (name "MANUFACTURER") "Microchip / Atmel"))
      (libsource (lib "Schlib1") (part "ATMEGA16U2-AU"))
    )
    (comp (ref "U2")
      (value "TL1963A-33DCQT")
      (footprint "DCQ (R-PDSO-G6)")
      (description "Single Output LDO, 1.5A, 3.3V Fast Trans")
      (fields (field (name "MANUFACTURER") "Texas Instruments"))
      (libsource (lib "Schlib1") (part "TL1963A-33DCQT"))
    )
    (comp (ref "U3")
      (value "ATMEGA328P-PU")
      (footprint "DIP28")
      (description "IC MCU 8BIT 32KB FLASH 28DIP")
      (fields (field (name "MANUFACTURER") "Microchip / Atmel"))
      (libsource (lib "Schlib1") (part "ATMEGA328P-PU"))
    )
    (comp (ref "U4")
      (value "SN74AUC1G08DBVR")
      (footprint "DBV-SOT-23-5")
      (description "LOGIC, 74AUC1G, AND GATE, SOT23-5")
      (fields (field (name "MANUFACTURER") "Texas Instruments"))
      (libsource (lib "Schlib1") (part "SN74AUC1G08DBVR"))
    )
    (comp (ref "U5")
      (value "SN74AUC1G08DBVR")
      (footprint "DBV-SOT-23-5")
      (description "LOGIC, 74AUC1G, AND GATE, SOT23-5")
      (fields (field (name "MANUFACTURER") "Texas Instruments"))
      (libsource (lib "Schlib1") (part "SN74AUC1G08DBVR"))
    )
    (comp (ref "U6")
      (value "SN74AUC1G08DBVR")
      (footprint "DBV-SOT-23-5")
      (description "LOGIC, 74AUC1G, AND GATE, SOT23-5")
      (fields (field (name "MANUFACTURER") "Texas Instruments"))
      (libsource (lib "Schlib1") (part "SN74AUC1G08DBVR"))
    )
    (comp (ref "U7")
      (value "SN74AUC1G08DBVR")
      (footprint "DBV-SOT-23-5")
      (description "LOGIC, 74AUC1G, AND GATE, SOT23-5")
      (fields (field (name "MANUFACTURER") "Texas Instruments"))
      (libsource (lib "Schlib1") (part "SN74AUC1G08DBVR"))
    )
    (comp (ref "Y1")
      (value "ABM11W-16.0000MHZ-8-B1U-T3")
      (footprint "ABM11W")
      (description "Iot Optimized 16MHZ 8PF Crystal")
      (fields (field (name "MANUFACTURER") "Abracon"))
      (libsource (lib "Schlib1") (part "ABM11W-16.0000MHZ-8-B1U-T3"))
    )
    (comp (ref "Y2")
      (value "ABM11W-16.0000MHZ-8-B1U-T3")
      (footprint "ABM11W")
      (description "Iot Optimized 16MHZ 8PF Crystal")
      (fields (field (name "MANUFACTURER") "Abracon"))
      (libsource (lib "Schlib1") (part "ABM11W-16.0000MHZ-8-B1U-T3"))
    )
    (comp (ref "Z1")
      (value "CGA0603MLC-05E")
      (footprint "Z0603")
      (description "ESD Suppressor TVS Bi-Dir 5V Automotive 2-Pin Case 0603(1608Metric) T/R")
      (fields (field (name "MANUFACTURER") "Bourns"))
      (libsource (lib "Schlib1") (part "CGA0603MLC-05E"))
    )
    (comp (ref "Z2")
      (value "CGA0603MLC-05E")
      (footprint "Z0603")
      (description "ESD Suppressor TVS Bi-Dir 5V Automotive 2-Pin Case 0603(1608Metric) T/R")
      (fields (field (name "MANUFACTURER") "Bourns"))
      (libsource (lib "Schlib1") (part "CGA0603MLC-05E"))
    )
  )
  (nets
    (net (code "1") (name "/+5V_USB") (class "Default")
      (node (ref "C7") (pin "1") (pinfunction "1_1") (pintype "passive"))
      (node (ref "J3") (pin "1") (pinfunction "1_1") (pintype "passive"))
      (node (ref "L1") (pin "1") (pinfunction "1_1") (pintype "passive"))
    )
    (net (code "2") (name "/3V3_16U2_UCAP") (class "Default")
      (node (ref "C5") (pin "2") (pinfunction "2_2") (pintype "passive"))
      (node (ref "R4") (pin "1") (pinfunction "1_1") (pintype "passive"))
      (node (ref "U1") (pin "27") (pinfunction "UCAP_27") (pintype "passive"))
    )
    (net (code "3") (name "/5{slash}3V3_16U2") (class "Default")
      (node (ref "C1") (pin "2") (pinfunction "2_2") (pintype "passive"))
      (node (ref "C2") (pin "2") (pinfunction "2_2") (pintype "passive"))
      (node (ref "C3") (pin "2") (pinfunction "2_2") (pintype "passive"))
      (node (ref "FB1") (pin "2") (pinfunction "2_2") (pintype "passive"))
      (node (ref "R4") (pin "2") (pinfunction "2_2") (pintype "passive"))
      (node (ref "U1") (pin "32") (pinfunction "AVCC_32") (pintype "passive"))
      (node (ref "U1") (pin "4") (pinfunction "VCC_4") (pintype "passive"))
    )
    (net (code "4") (name "/5{slash}3V3_328P_AVCC") (class "Default")
      (node (ref "C22") (pin "2") (pinfunction "2_2") (pintype "passive"))
      (node (ref "C23") (pin "2") (pinfunction "2_2") (pintype "passive"))
      (node (ref "FB3") (pin "2") (pinfunction "2_2") (pintype "passive"))
      (node (ref "U3") (pin "20") (pinfunction "AVCC_20") (pintype "passive"))
    )
    (net (code "5") (name "/5{slash}3V3_328P_VCC") (class "Default")
      (node (ref "C19") (pin "2") (pinfunction "2_2") (pintype "passive"))
      (node (ref "C20") (pin "2") (pinfunction "2_2") (pintype "passive"))
      (node (ref "FB2") (pin "2") (pinfunction "2_2") (pintype "passive"))
      (node (ref "U3") (pin "7") (pinfunction "VCC_7") (pintype "passive"))
    )
    (net (code "6") (name "/16U2PROG_328P_~{RESET}n") (class "Default")
      (node (ref "D2") (pin "1") (pinfunction "Cathode_1") (pintype "passive"))
      (node (ref "JP2") (pin "2") (pinfunction "2_2") (pintype "passive"))
      (node (ref "R1") (pin "1") (pinfunction "1_1") (pintype "passive"))
      (node (ref "U1") (pin "10") (pinfunction "(INT5/_AIN3)_PD4_10") (pintype "passive"))
      (node (ref "U1") (pin "13") (pinfunction "/_HWB_/_AIN6_/_T0_/_INT7)_PD7_13") (pintype "passive"))
    )
    (net (code "7") (name "/16U2_16MHZ_XTAL1") (class "Default")
      (node (ref "C10") (pin "2") (pinfunction "2_2") (pintype "passive"))
      (node (ref "R7") (pin "1") (pinfunction "1_1") (pintype "passive"))
      (node (ref "U1") (pin "1") (pinfunction "XTAL1_1") (pintype "passive"))
      (node (ref "Y1") (pin "3") (pinfunction "3_3") (pintype "passive"))
    )
    (net (code "8") (name "/16U2_16MHZ_XTAL2") (class "Default")
      (node (ref "C9") (pin "2") (pinfunction "2_2") (pintype "passive"))
      (node (ref "R7") (pin "2") (pinfunction "2_2") (pintype "passive"))
      (node (ref "U1") (pin "2") (pinfunction "(PC0)_XTAL2_2") (pintype "passive"))
      (node (ref "Y1") (pin "1") (pinfunction "1_1") (pintype "passive"))
    )
    (net (code "9") (name "/16U2_BUF_~{RESET}n") (class "Default")
      (node (ref "C31") (pin "1") (pinfunction "1_1") (pintype "passive"))
      (node (ref "R26") (pin "2") (pinfunction "2_2") (pintype "passive"))
      (node (ref "U5") (pin "1") (pinfunction "1_1") (pintype "passive"))
      (node (ref "U5") (pin "2") (pinfunction "2_2") (pintype "passive"))
    )
    (net (code "10") (name "/16U2_HDR_~{RESET}n") (class "Default")
      (node (ref "J2") (pin "5") (pinfunction "5_5") (pintype "passive"))
      (node (ref "JP1") (pin "3") (pinfunction "3_3") (pintype "passive"))
    )
    (net (code "11") (name "/16U2_MISO") (class "Default")
      (node (ref "J2") (pin "1") (pinfunction "1_1") (pintype "passive"))
      (node (ref "U1") (pin "17") (pinfunction "PB3_(PDO_/_MISO_/_PCINT3)_17") (pintype "passive"))
    )
    (net (code "12") (name "/16U2_MOSI") (class "Default")
      (node (ref "J2") (pin "4") (pinfunction "4_4") (pintype "passive"))
      (node (ref "U1") (pin "16") (pinfunction "(PDI_/_MOSI_/_PCINT2)_PB2_16") (pintype "passive"))
    )
    (net (code "13") (name "/16U2_PB4") (class "Default")
      (node (ref "J1") (pin "1") (pinfunction "1_1") (pintype "passive"))
      (node (ref "JP1") (pin "2") (pinfunction "2_2") (pintype "passive"))
      (node (ref "U1") (pin "18") (pinfunction "PB4_(T1_/_PCINT4)_18") (pintype "passive"))
    )
    (net (code "14") (name "/16U2_PB5") (class "Default")
      (node (ref "J1") (pin "3") (pinfunction "3_3") (pintype "passive"))
      (node (ref "U1") (pin "19") (pinfunction "PB5_(PCINT5)_19") (pintype "passive"))
    )
    (net (code "15") (name "/16U2_PB6") (class "Default")
      (node (ref "J1") (pin "2") (pinfunction "2_2") (pintype "passive"))
      (node (ref "U1") (pin "20") (pinfunction "PB6_(PCINT6)_20") (pintype "passive"))
    )
    (net (code "16") (name "/16U2_PB7") (class "Default")
      (node (ref "J1") (pin "4") (pinfunction "4_4") (pintype "passive"))
      (node (ref "U1") (pin "21") (pinfunction "PB7_(PCINT7_/_OC.0A_/_OC.1C)_21") (pintype "passive"))
    )
    (net (code "17") (name "/16U2_RXD") (class "Default")
      (node (ref "R12") (pin "1") (pinfunction "1_1") (pintype "passive"))
      (node (ref "U1") (pin "8") (pinfunction "(RXD1_/_AIN1_/_INT2)_PD2_8") (pintype "passive"))
    )
    (net (code "18") (name "/16U2_SCLK") (class "Default")
      (node (ref "J2") (pin "3") (pinfunction "3_3") (pintype "passive"))
      (node (ref "R6") (pin "2") (pinfunction "2_2") (pintype "passive"))
    )
    (net (code "19") (name "/16U2_SCLK_R") (class "Default")
      (node (ref "R6") (pin "1") (pinfunction "1_1") (pintype "passive"))
      (node (ref "U1") (pin "15") (pinfunction "(SCLK_/_PCINT1)_PB1_15") (pintype "passive"))
    )
    (net (code "20") (name "/16U2_TXD") (class "Default")
      (node (ref "R11") (pin "1") (pinfunction "1_1") (pintype "passive"))
      (node (ref "U1") (pin "9") (pinfunction "(TXD1_/_INT3)_PD3_9") (pintype "passive"))
    )
    (net (code "21") (name "/16U2_TX_LED") (class "Default")
      (node (ref "D1") (pin "1") (pinfunction "Cathode_1") (pintype "passive"))
      (node (ref "U1") (pin "11") (pinfunction "(XCK_AIN4_/_PCINT12)_PD5_11") (pintype "passive"))
    )
    (net (code "22") (name "/16U2_~{RESET}n") (class "Default")
      (node (ref "JP1") (pin "4") (pinfunction "4_4") (pintype "passive"))
      (node (ref "R5") (pin "1") (pinfunction "1_1") (pintype "passive"))
      (node (ref "U1") (pin "24") (pinfunction "~{RESET}_(PC1_/_dW)_24") (pintype "passive"))
      (node (ref "U5") (pin "4") (pinfunction "4_4") (pintype "passive"))
    )
    (net (code "23") (name "/328P_16MHZ_XTAL1") (class "Default")
      (node (ref "C27") (pin "2") (pinfunction "2_2") (pintype "passive"))
      (node (ref "R20") (pin "1") (pinfunction "1_1") (pintype "passive"))
      (node (ref "U3") (pin "9") (pinfunction "(PCINT6/XTAL1/TOSC1)_PB6_9") (pintype "passive"))
      (node (ref "Y2") (pin "3") (pinfunction "3_3") (pintype "passive"))
    )
    (net (code "24") (name "/328P_16MHZ_XTAL2") (class "Default")
      (node (ref "C26") (pin "2") (pinfunction "2_2") (pintype "passive"))
      (node (ref "R20") (pin "2") (pinfunction "2_2") (pintype "passive"))
      (node (ref "U3") (pin "10") (pinfunction "(PCINT7/XTAL2/TOSC2)_PB7_10") (pintype "passive"))
      (node (ref "Y2") (pin "1") (pinfunction "1_1") (pintype "passive"))
    )
    (net (code "25") (name "/328P_AUTO~{RESET}n") (class "Default")
      (node (ref "C11") (pin "2") (pinfunction "2_2") (pintype "passive"))
      (node (ref "R21") (pin "1") (pinfunction "1_1") (pintype "passive"))
      (node (ref "U6") (pin "1") (pinfunction "1_1") (pintype "passive"))
    )
    (net (code "26") (name "/328P_BUF_~{RESET}n") (class "Default")
      (node (ref "C32") (pin "1") (pinfunction "1_1") (pintype "passive"))
      (node (ref "R27") (pin "2") (pinfunction "2_2") (pintype "passive"))
      (node (ref "U6") (pin "2") (pinfunction "2_2") (pintype "passive"))
    )
    (net (code "27") (name "/328P_~{RESET}n") (class "Default")
      (node (ref "J6") (pin "5") (pinfunction "5_5") (pintype "passive"))
      (node (ref "J7") (pin "3") (pinfunction "3_3") (pintype "passive"))
      (node (ref "JP1") (pin "1") (pinfunction "1_1") (pintype "passive"))
      (node (ref "R17") (pin "1") (pinfunction "1_1") (pintype "passive"))
      (node (ref "U3") (pin "1") (pinfunction "(PCINT14/RESET)_PC6_1") (pintype "passive"))
      (node (ref "U6") (pin "4") (pinfunction "4_4") (pintype "passive"))
    )
    (net (code "28") (name "/AD0") (class "Default")
      (node (ref "J9") (pin "1") (pinfunction "1_1") (pintype "passive"))
      (node (ref "U3") (pin "23") (pinfunction "PC0_(ADC0/PCINT8)_23") (pintype "passive"))
    )
    (net (code "29") (name "/AD1") (class "Default")
      (node (ref "J9") (pin "2") (pinfunction "2_2") (pintype "passive"))
      (node (ref "U3") (pin "24") (pinfunction "PC1_(ADC1/PCINT9)_24") (pintype "passive"))
    )
    (net (code "30") (name "/AD2") (class "Default")
      (node (ref "J9") (pin "3") (pinfunction "3_3") (pintype "passive"))
      (node (ref "U3") (pin "25") (pinfunction "PC2_(ADC2/PCINT10)_25") (pintype "passive"))
    )
    (net (code "31") (name "/AD3") (class "Default")
      (node (ref "J9") (pin "4") (pinfunction "4_4") (pintype "passive"))
      (node (ref "U3") (pin "26") (pinfunction "PC3_(ADC3/PCINT11)_26") (pintype "passive"))
    )
    (net (code "32") (name "/AD4{slash}SDA") (class "Default")
      (node (ref "J8") (pin "9") (pinfunction "9_9") (pintype "passive"))
      (node (ref "J9") (pin "5") (pinfunction "5_5") (pintype "passive"))
      (node (ref "U3") (pin "27") (pinfunction "PC4_(ADC4/SDA/PCINT12)_27") (pintype "passive"))
    )
    (net (code "33") (name "/AD5{slash}SCL") (class "Default")
      (node (ref "J8") (pin "10") (pinfunction "10_10") (pintype "passive"))
      (node (ref "J9") (pin "6") (pinfunction "6_6") (pintype "passive"))
      (node (ref "U3") (pin "28") (pinfunction "PC5_(ADC5/SCL/PCINT13)_28") (pintype "passive"))
    )
    (net (code "34") (name "/BUTTON_~{RESET}n") (class "Default")
      (node (ref "D6") (pin "2") (pinfunction "Anode_2") (pintype "passive"))
      (node (ref "R23") (pin "1") (pinfunction "1_1") (pintype "passive"))
      (node (ref "R27") (pin "1") (pinfunction "1_1") (pintype "passive"))
      (node (ref "SW1") (pin "1") (pinfunction "1_1") (pintype "passive"))
      (node (ref "SW1") (pin "2") (pinfunction "2_2") (pintype "passive"))
    )
    (net (code "35") (name "/CON_USB_N") (class "Default")
      (node (ref "J3") (pin "2") (pinfunction "2_2") (pintype "passive"))
      (node (ref "R8") (pin "1") (pinfunction "1_1") (pintype "passive"))
      (node (ref "Z1") (pin "2") (pinfunction "2_2") (pintype "passive"))
    )
    (net (code "36") (name "/CON_USB_P") (class "Default")
      (node (ref "J3") (pin "3") (pinfunction "3_3") (pintype "passive"))
      (node (ref "R9") (pin "1") (pinfunction "1_1") (pintype "passive"))
      (node (ref "Z2") (pin "2") (pinfunction "2_2") (pintype "passive"))
    )
    (net (code "37") (name "/IO0") (class "Default")
      (node (ref "J10") (pin "1") (pinfunction "1_1") (pintype "passive"))
      (node (ref "R11") (pin "2") (pinfunction "2_2") (pintype "passive"))
      (node (ref "U3") (pin "2") (pinfunction "(PCINT16/RXD)_PD0_2") (pintype "passive"))
    )
    (net (code "38") (name "/IO1") (class "Default")
      (node (ref "J10") (pin "2") (pinfunction "2_2") (pintype "passive"))
      (node (ref "R12") (pin "2") (pinfunction "2_2") (pintype "passive"))
      (node (ref "U3") (pin "3") (pinfunction "(PCINT17/TXD)_PD1_3") (pintype "passive"))
    )
    (net (code "39") (name "/IO2") (class "Default")
      (node (ref "J10") (pin "3") (pinfunction "3_3") (pintype "passive"))
      (node (ref "U3") (pin "4") (pinfunction "(PCINT18/INT0)_PD2_4") (pintype "passive"))
    )
    (net (code "40") (name "/IO3") (class "Default")
      (node (ref "J10") (pin "4") (pinfunction "4_4") (pintype "passive"))
      (node (ref "U3") (pin "5") (pinfunction "(PCINT19/OC2B/INT1)_PD3_5") (pintype "passive"))
    )
    (net (code "41") (name "/IO4") (class "Default")
      (node (ref "J10") (pin "5") (pinfunction "5_5") (pintype "passive"))
      (node (ref "U3") (pin "6") (pinfunction "(PCINT20/XCK/T0)_PD4_6") (pintype "passive"))
    )
    (net (code "42") (name "/IO5") (class "Default")
      (node (ref "J10") (pin "6") (pinfunction "6_6") (pintype "passive"))
      (node (ref "U3") (pin "11") (pinfunction "(PCINT21/OC0B/T1)_PD5_11") (pintype "passive"))
    )
    (net (code "43") (name "/IO6") (class "Default")
      (node (ref "J10") (pin "7") (pinfunction "7_7") (pintype "passive"))
      (node (ref "U3") (pin "12") (pinfunction "(PCINT22/OC0A/AIN0)_PD6_12") (pintype "passive"))
    )
    (net (code "44") (name "/IO7") (class "Default")
      (node (ref "J10") (pin "8") (pinfunction "8_8") (pintype "passive"))
      (node (ref "U3") (pin "13") (pinfunction "(PCINT23/AIN1)_PD7_13") (pintype "passive"))
    )
    (net (code "45") (name "/IO8") (class "Default")
      (node (ref "J8") (pin "1") (pinfunction "1_1") (pintype "passive"))
      (node (ref "R25") (pin "2") (pinfunction "2_2") (pintype "passive"))
      (node (ref "U3") (pin "14") (pinfunction "(PCINT0/CLKO/ICP1)_PB0_14") (pintype "passive"))
    )
    (net (code "46") (name "/IO9") (class "Default")
      (node (ref "J8") (pin "2") (pinfunction "2_2") (pintype "passive"))
      (node (ref "U3") (pin "15") (pinfunction "PB1_(OC1A/PCINT1)_15") (pintype "passive"))
    )
    (net (code "47") (name "/MISO") (class "Default")
      (node (ref "J6") (pin "1") (pinfunction "1_1") (pintype "passive"))
      (node (ref "J8") (pin "5") (pinfunction "5_5") (pintype "passive"))
      (node (ref "U3") (pin "18") (pinfunction "PB4_(MISO/PCINT4)_18") (pintype "passive"))
    )
    (net (code "48") (name "/SCK") (class "Default")
      (node (ref "J6") (pin "3") (pinfunction "3_3") (pintype "passive"))
      (node (ref "J8") (pin "6") (pinfunction "6_6") (pintype "passive"))
      (node (ref "R16") (pin "2") (pinfunction "2_2") (pintype "passive"))
      (node (ref "U4") (pin "1") (pinfunction "1_1") (pintype "passive"))
      (node (ref "U4") (pin "2") (pinfunction "2_2") (pintype "passive"))
    )
    (net (code "49") (name "/SCK_R") (class "Default")
      (node (ref "R16") (pin "1") (pinfunction "1_1") (pintype "passive"))
      (node (ref "U3") (pin "19") (pinfunction "PB5_(SCK/PCINT5)_19") (pintype "passive"))
    )
    (net (code "50") (name "/SS") (class "Default")
      (node (ref "J8") (pin "3") (pinfunction "3_3") (pintype "passive"))
      (node (ref "U3") (pin "16") (pinfunction "PB2_(SS/OC1B/PCINT2)_16") (pintype "passive"))
    )
    (net (code "51") (name "/USB_N") (class "Default")
      (node (ref "R8") (pin "2") (pinfunction "2_2") (pintype "passive"))
      (node (ref "U1") (pin "30") (pinfunction "D-_30") (pintype "passive"))
    )
    (net (code "52") (name "/USB_P") (class "Default")
      (node (ref "R9") (pin "2") (pinfunction "2_2") (pintype "passive"))
      (node (ref "U1") (pin "29") (pinfunction "D+_29") (pintype "passive"))
    )
    (net (code "53") (name "/USER_BUTTON") (class "Default")
      (node (ref "R24") (pin "1") (pinfunction "1_1") (pintype "passive"))
      (node (ref "R28") (pin "1") (pinfunction "1_1") (pintype "passive"))
      (node (ref "SW2") (pin "1") (pinfunction "1_1") (pintype "passive"))
      (node (ref "SW2") (pin "2") (pinfunction "2_2") (pintype "passive"))
    )
    (net (code "54") (name "/USER_BUTTON_BUF") (class "Default")
      (node (ref "C33") (pin "1") (pinfunction "1_1") (pintype "passive"))
      (node (ref "R28") (pin "2") (pinfunction "2_2") (pintype "passive"))
      (node (ref "U7") (pin "1") (pinfunction "1_1") (pintype "passive"))
      (node (ref "U7") (pin "2") (pinfunction "2_2") (pintype "passive"))
    )
    (net (code "55") (name "3V3") (class "Default")
      (node (ref "C13") (pin "2") (pinfunction "2_2") (pintype "passive"))
      (node (ref "C15") (pin "2") (pinfunction "2_2") (pintype "passive"))
      (node (ref "J7") (pin "4") (pinfunction "4_4") (pintype "passive"))
      (node (ref "JP3") (pin "1") (pinfunction "1_1") (pintype "passive"))
      (node (ref "R15") (pin "2") (pinfunction "2_2") (pintype "passive"))
      (node (ref "U2") (pin "4") (pinfunction "OUT_4") (pintype "passive"))
      (node (ref "U2") (pin "5") (pinfunction "ADJ_5") (pintype "passive"))
    )
    (net (code "56") (name "5V") (class "Default")
      (node (ref "C12") (pin "2") (pinfunction "2_2") (pintype "passive"))
      (node (ref "C16") (pin "2") (pinfunction "2_2") (pintype "passive"))
      (node (ref "C4") (pin "2") (pinfunction "2_2") (pintype "passive"))
      (node (ref "C8") (pin "1") (pinfunction "1_1") (pintype "passive"))
      (node (ref "J4") (pin "1") (pinfunction "1_1") (pintype "passive"))
      (node (ref "J7") (pin "5") (pinfunction "5_5") (pintype "passive"))
      (node (ref "JP3") (pin "3") (pinfunction "3_3") (pintype "passive"))
      (node (ref "L1") (pin "2") (pinfunction "2_2") (pintype "passive"))
      (node (ref "R14") (pin "1") (pinfunction "1_1") (pintype "passive"))
      (node (ref "U1") (pin "31") (pinfunction "UVCC_31") (pintype "passive"))
      (node (ref "U2") (pin "1") (pinfunction "~{SHDN}_1") (pintype "passive"))
      (node (ref "U2") (pin "2") (pinfunction "IN_2") (pintype "passive"))
    )
    (net (code "57") (name "5V{slash}3V3") (class "Default")
      (node (ref "C14") (pin "2") (pinfunction "2_2") (pintype "passive"))
      (node (ref "C17") (pin "2") (pinfunction "2_2") (pintype "passive"))
      (node (ref "C18") (pin "2") (pinfunction "2_2") (pintype "passive"))
      (node (ref "C25") (pin "2") (pinfunction "2_2") (pintype "passive"))
      (node (ref "C28") (pin "2") (pinfunction "2_2") (pintype "passive"))
      (node (ref "C29") (pin "2") (pinfunction "2_2") (pintype "passive"))
      (node (ref "C30") (pin "2") (pinfunction "2_2") (pintype "passive"))
      (node (ref "C6") (pin "2") (pinfunction "2_2") (pintype "passive"))
      (node (ref "D5") (pin "1") (pinfunction "Cathode_1") (pintype "passive"))
      (node (ref "D6") (pin "1") (pinfunction "Cathode_1") (pintype "passive"))
      (node (ref "FB1") (pin "1") (pinfunction "1_1") (pintype "passive"))
      (node (ref "FB2") (pin "1") (pinfunction "1_1") (pintype "passive"))
      (node (ref "FB3") (pin "1") (pinfunction "1_1") (pintype "passive"))
      (node (ref "J2") (pin "2") (pinfunction "2_2") (pintype "passive"))
      (node (ref "J6") (pin "2") (pinfunction "2_2") (pintype "passive"))
      (node (ref "J6") (pin "4") (pinfunction "4_4") (pintype "passive"))
      (node (ref "J7") (pin "2") (pinfunction "2_2") (pintype "passive"))
      (node (ref "J8") (pin "4") (pinfunction "4_4") (pintype "passive"))
      (node (ref "JP3") (pin "2") (pinfunction "2_2") (pintype "passive"))
      (node (ref "R1") (pin "2") (pinfunction "2_2") (pintype "passive"))
      (node (ref "R14") (pin "2") (pinfunction "2_2") (pintype "passive"))
      (node (ref "R15") (pin "1") (pinfunction "1_1") (pintype "passive"))
      (node (ref "R17") (pin "2") (pinfunction "2_2") (pintype "passive"))
      (node (ref "R18") (pin "1") (pinfunction "1_1") (pintype "passive"))
      (node (ref "R19") (pin "1") (pinfunction "1_1") (pintype "passive"))
      (node (ref "R2") (pin "2") (pinfunction "2_2") (pintype "passive"))
      (node (ref "R21") (pin "2") (pinfunction "2_2") (pintype "passive"))
      (node (ref "R22") (pin "2") (pinfunction "2_2") (pintype "passive"))
      (node (ref "R23") (pin "2") (pinfunction "2_2") (pintype "passive"))
      (node (ref "R24") (pin "2") (pinfunction "2_2") (pintype "passive"))
      (node (ref "R3") (pin "2") (pinfunction "2_2") (pintype "passive"))
      (node (ref "R5") (pin "2") (pinfunction "2_2") (pintype "passive"))
      (node (ref "U3") (pin "17") (pinfunction "PB3_(MOSI/OC2A/PCINT3)_17") (pintype "passive"))
      (node (ref "U4") (pin "5") (pinfunction "5_5") (pintype "passive"))
      (node (ref "U5") (pin "5") (pinfunction "5_5") (pintype "passive"))
      (node (ref "U6") (pin "5") (pinfunction "5_5") (pintype "passive"))
      (node (ref "U7") (pin "5") (pinfunction "5_5") (pintype "passive"))
    )
    (net (code "58") (name "AREF") (class "Default")
      (node (ref "C21") (pin "2") (pinfunction "2_2") (pintype "passive"))
      (node (ref "C24") (pin "2") (pinfunction "2_2") (pintype "passive"))
      (node (ref "J8") (pin "8") (pinfunction "8_8") (pintype "passive"))
      (node (ref "U3") (pin "21") (pinfunction "AREF_21") (pintype "passive"))
    )
    (net (code "59") (name "GND") (class "Default")
      (node (ref "C1") (pin "1") (pinfunction "1_1") (pintype "passive"))
      (node (ref "C10") (pin "1") (pinfunction "1_1") (pintype "passive"))
      (node (ref "C12") (pin "1") (pinfunction "1_1") (pintype "passive"))
      (node (ref "C13") (pin "1") (pinfunction "1_1") (pintype "passive"))
      (node (ref "C14") (pin "1") (pinfunction "1_1") (pintype "passive"))
      (node (ref "C15") (pin "1") (pinfunction "1_1") (pintype "passive"))
      (node (ref "C16") (pin "1") (pinfunction "1_1") (pintype "passive"))
      (node (ref "C17") (pin "1") (pinfunction "1_1") (pintype "passive"))
      (node (ref "C18") (pin "1") (pinfunction "1_1") (pintype "passive"))
      (node (ref "C19") (pin "1") (pinfunction "1_1") (pintype "passive"))
      (node (ref "C2") (pin "1") (pinfunction "1_1") (pintype "passive"))
      (node (ref "C20") (pin "1") (pinfunction "1_1") (pintype "passive"))
      (node (ref "C21") (pin "1") (pinfunction "1_1") (pintype "passive"))
      (node (ref "C22") (pin "1") (pinfunction "1_1") (pintype "passive"))
      (node (ref "C23") (pin "1") (pinfunction "1_1") (pintype "passive"))
      (node (ref "C24") (pin "1") (pinfunction "1_1") (pintype "passive"))
      (node (ref "C25") (pin "1") (pinfunction "1_1") (pintype "passive"))
      (node (ref "C26") (pin "1") (pinfunction "1_1") (pintype "passive"))
      (node (ref "C27") (pin "1") (pinfunction "1_1") (pintype "passive"))
      (node (ref "C28") (pin "1") (pinfunction "1_1") (pintype "passive"))
      (node (ref "C29") (pin "1") (pinfunction "1_1") (pintype "passive"))
      (node (ref "C3") (pin "1") (pinfunction "1_1") (pintype "passive"))
      (node (ref "C30") (pin "1") (pinfunction "1_1") (pintype "passive"))
      (node (ref "C31") (pin "2") (pinfunction "2_2") (pintype "passive"))
      (node (ref "C32") (pin "2") (pinfunction "2_2") (pintype "passive"))
      (node (ref "C33") (pin "2") (pinfunction "2_2") (pintype "passive"))
      (node (ref "C5") (pin "1") (pinfunction "1_1") (pintype "passive"))
      (node (ref "C6") (pin "1") (pinfunction "1_1") (pintype "passive"))
      (node (ref "C7") (pin "2") (pinfunction "2_2") (pintype "passive"))
      (node (ref "C8") (pin "2") (pinfunction "2_2") (pintype "passive"))
      (node (ref "C9") (pin "1") (pinfunction "1_1") (pintype "passive"))
      (node (ref "D4") (pin "1") (pinfunction "Cathode_1") (pintype "passive"))
      (node (ref "J2") (pin "6") (pinfunction "6_6") (pintype "passive"))
      (node (ref "J3") (pin "10") (pinfunction "10_10") (pintype "passive"))
      (node (ref "J3") (pin "11") (pinfunction "11_11") (pintype "passive"))
      (node (ref "J3") (pin "5") (pinfunction "5_5") (pintype "passive"))
      (node (ref "J3") (pin "6") (pinfunction "6_6") (pintype "passive"))
      (node (ref "J3") (pin "7") (pinfunction "7_7") (pintype "passive"))
      (node (ref "J3") (pin "8") (pinfunction "8_8") (pintype "passive"))
      (node (ref "J3") (pin "9") (pinfunction "9_9") (pintype "passive"))
      (node (ref "J5") (pin "1") (pinfunction "1_1") (pintype "passive"))
      (node (ref "J6") (pin "6") (pinfunction "6_6") (pintype "passive"))
      (node (ref "J7") (pin "6") (pinfunction "6_6") (pintype "passive"))
      (node (ref "J7") (pin "7") (pinfunction "7_7") (pintype "passive"))
      (node (ref "J8") (pin "7") (pinfunction "7_7") (pintype "passive"))
      (node (ref "R10") (pin "2") (pinfunction "2_2") (pintype "passive"))
      (node (ref "R13") (pin "1") (pinfunction "1_1") (pintype "passive"))
      (node (ref "SW1") (pin "3") (pinfunction "3_3") (pintype "passive"))
      (node (ref "SW1") (pin "4") (pinfunction "4_4") (pintype "passive"))
      (node (ref "SW2") (pin "3") (pinfunction "3_3") (pintype "passive"))
      (node (ref "SW2") (pin "4") (pinfunction "4_4") (pintype "passive"))
      (node (ref "U1") (pin "28") (pinfunction "UGND_28") (pintype "passive"))
      (node (ref "U1") (pin "3") (pinfunction "GND_3") (pintype "passive"))
      (node (ref "U2") (pin "3") (pinfunction "GND_3") (pintype "passive"))
      (node (ref "U2") (pin "6") (pinfunction "EPAD_6") (pintype "passive"))
      (node (ref "U3") (pin "22") (pinfunction "GND_22") (pintype "passive"))
      (node (ref "U3") (pin "8") (pinfunction "GND_8") (pintype "passive"))
      (node (ref "U4") (pin "3") (pinfunction "3_3") (pintype "passive"))
      (node (ref "U5") (pin "3") (pinfunction "3_3") (pintype "passive"))
      (node (ref "U6") (pin "3") (pinfunction "3_3") (pintype "passive"))
      (node (ref "U7") (pin "3") (pinfunction "3_3") (pintype "passive"))
      (node (ref "Y1") (pin "2") (pinfunction "2_2") (pintype "passive"))
      (node (ref "Y2") (pin "2") (pinfunction "2_2") (pintype "passive"))
      (node (ref "Z1") (pin "1") (pinfunction "1_1") (pintype "passive"))
      (node (ref "Z2") (pin "1") (pinfunction "1_1") (pintype "passive"))
    )
    (net (code "60") (name "Net-(C11-Pad1)") (class "Default")
      (node (ref "C11") (pin "1") (pinfunction "1_1") (pintype "passive"))
      (node (ref "JP2") (pin "1") (pinfunction "1_1") (pintype "passive"))
    )
    (net (code "61") (name "Net-(D1-Anode)") (class "Default")
      (node (ref "D1") (pin "2") (pinfunction "Anode_2") (pintype "passive"))
      (node (ref "R2") (pin "1") (pinfunction "1_1") (pintype "passive"))
    )
    (net (code "62") (name "Net-(D2-Anode)") (class "Default")
      (node (ref "D2") (pin "2") (pinfunction "Anode_2") (pintype "passive"))
      (node (ref "R3") (pin "1") (pinfunction "1_1") (pintype "passive"))
    )
    (net (code "63") (name "Net-(D3-Anode)") (class "Default")
      (node (ref "D3") (pin "2") (pinfunction "Anode_2") (pintype "passive"))
      (node (ref "R18") (pin "2") (pinfunction "2_2") (pintype "passive"))
    )
    (net (code "64") (name "Net-(D3-Cathode)") (class "Default")
      (node (ref "D3") (pin "1") (pinfunction "Cathode_1") (pintype "passive"))
      (node (ref "U4") (pin "4") (pinfunction "4_4") (pintype "passive"))
    )
    (net (code "65") (name "Net-(D4-Anode)") (class "Default")
      (node (ref "D4") (pin "2") (pinfunction "Anode_2") (pintype "passive"))
      (node (ref "R19") (pin "2") (pinfunction "2_2") (pintype "passive"))
    )
    (net (code "66") (name "Net-(D5-Anode)") (class "Default")
      (node (ref "D5") (pin "2") (pinfunction "Anode_2") (pintype "passive"))
      (node (ref "R22") (pin "1") (pinfunction "1_1") (pintype "passive"))
      (node (ref "R26") (pin "1") (pinfunction "1_1") (pintype "passive"))
    )
    (net (code "67") (name "Net-(J3-Pad4)") (class "Default")
      (node (ref "J3") (pin "4") (pinfunction "4_4") (pintype "passive"))
      (node (ref "R10") (pin "1") (pinfunction "1_1") (pintype "passive"))
    )
    (net (code "68") (name "Net-(JP2-Pad3)") (class "Default")
      (node (ref "JP2") (pin "3") (pinfunction "3_3") (pintype "passive"))
      (node (ref "R13") (pin "2") (pinfunction "2_2") (pintype "passive"))
    )
    (net (code "69") (name "Net-(R25-Pad1)") (class "Default")
      (node (ref "R25") (pin "1") (pinfunction "1_1") (pintype "passive"))
      (node (ref "U7") (pin "4") (pinfunction "4_4") (pintype "passive"))
    )
    (net (code "70") (name "unconnected-(C4-Pad1)") (class "Default")
      (node (ref "C4") (pin "1") (pinfunction "1_1") (pintype "passive"))
    )
    (net (code "71") (name "unconnected-(J7-Pad1)") (class "Default")
      (node (ref "J7") (pin "1") (pinfunction "1_1") (pintype "passive+no_connect"))
    )
    (net (code "72") (name "unconnected-(J7-Pad8)") (class "Default")
      (node (ref "J7") (pin "8") (pinfunction "8_8") (pintype "passive+no_connect"))
    )
    (net (code "73") (name "unconnected-(MH1-Pad1)") (class "Default")
      (node (ref "MH1") (pin "1") (pinfunction "1_1") (pintype "passive"))
    )
    (net (code "74") (name "unconnected-(MH2-Pad1)") (class "Default")
      (node (ref "MH2") (pin "1") (pinfunction "1_1") (pintype "passive"))
    )
    (net (code "75") (name "unconnected-(MH3-Pad1)") (class "Default")
      (node (ref "MH3") (pin "1") (pinfunction "1_1") (pintype "passive"))
    )
    (net (code "76") (name "unconnected-(MH4-Pad1)") (class "Default")
      (node (ref "MH4") (pin "1") (pinfunction "1_1") (pintype "passive"))
    )
    (net (code "77") (name "unconnected-(U1-(AIN0_{slash}_INT1)_PD1-Pad7)") (class "Default")
      (node (ref "U1") (pin "7") (pinfunction "(AIN0_/_INT1)_PD1_7") (pintype "passive"))
    )
    (net (code "78") (name "unconnected-(U1-(OC.0B_{slash}_INT0)_PD0-Pad6)") (class "Default")
      (node (ref "U1") (pin "6") (pinfunction "(OC.0B_/_INT0)_PD0_6") (pintype "passive"))
    )
    (net (code "79") (name "unconnected-(U1-(PCINT11_{slash}AIN2_)_PC2-Pad5)") (class "Default")
      (node (ref "U1") (pin "5") (pinfunction "(PCINT11_/AIN2_)_PC2_5") (pintype "passive+no_connect"))
    )
    (net (code "80") (name "unconnected-(U1-(RTS_{slash}_AIN5_{slash}_INT6)_PD6-Pad12)") (class "Default")
      (node (ref "U1") (pin "12") (pinfunction "(RTS_/_AIN5_/_INT6)_PD6_12") (pintype "passive+no_connect"))
    )
    (net (code "81") (name "unconnected-(U1-(SS_{slash}_PCINT0)_PB0-Pad14)") (class "Default")
      (node (ref "U1") (pin "14") (pinfunction "(SS_/_PCINT0)_PB0_14") (pintype "passive+no_connect"))
    )
    (net (code "82") (name "unconnected-(U1-PC4_(PCINT10)-Pad26)") (class "Default")
      (node (ref "U1") (pin "26") (pinfunction "PC4_(PCINT10)_26") (pintype "passive+no_connect"))
    )
    (net (code "83") (name "unconnected-(U1-PC5_(_PCINT9{slash}_OC.1B)-Pad25)") (class "Default")
      (node (ref "U1") (pin "25") (pinfunction "PC5_(_PCINT9/_OC.1B)_25") (pintype "passive+no_connect"))
    )
    (net (code "84") (name "unconnected-(U1-PC6_(OC.1A_{slash}_PCINT8)-Pad23)") (class "Default")
      (node (ref "U1") (pin "23") (pinfunction "PC6_(OC.1A_/_PCINT8)_23") (pintype "passive+no_connect"))
    )
    (net (code "85") (name "unconnected-(U1-PC7_(INT4_{slash}_ICP1_{slash}_CLKO)-Pad22)") (class "Default")
      (node (ref "U1") (pin "22") (pinfunction "PC7_(INT4_/_ICP1_/_CLKO)_22") (pintype "passive+no_connect"))
    )
  )
)
